# 13_USB3_0_power.net
KiCad netlist of a schematic drawn in Altium Designer
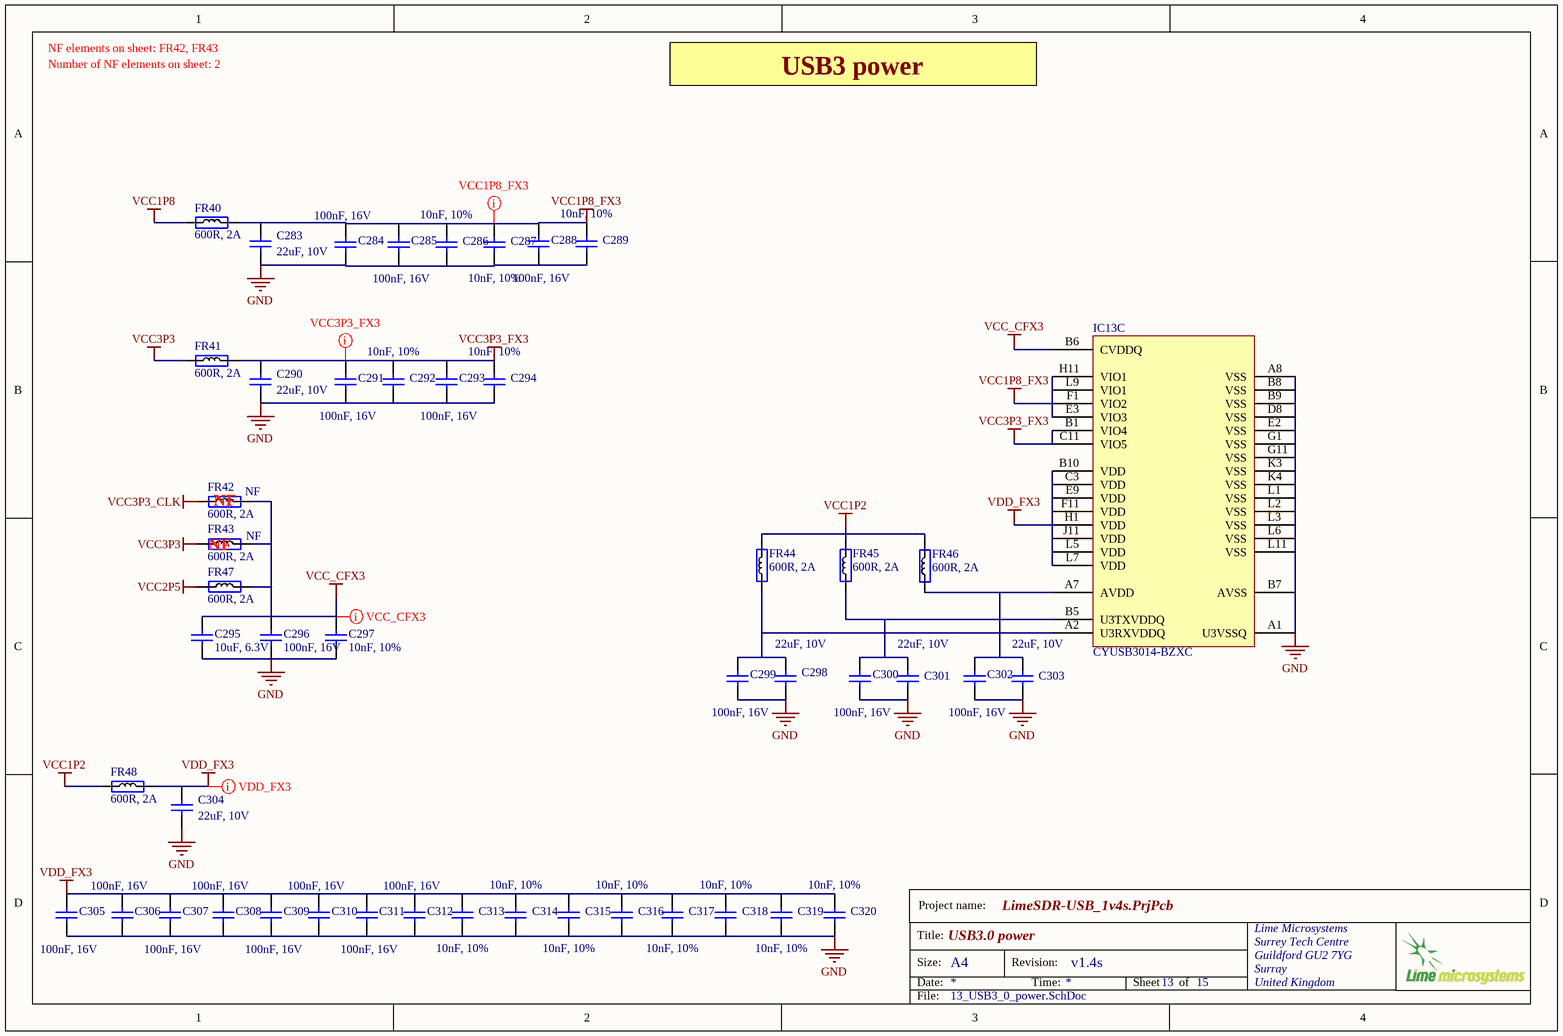
[diagram p0: 13_USB3_0_power.SchDoc]

(export (version "E")
  (design (tool "Eeschema 10.0.6"))
  (components
    (comp (ref "C283")
      (value "22uF, 10V")
      (footprint "CAP0603")
      (fields (field (name "TOLERANCE") "20 %") (field (name "MANUFACTURER") "TDK"))
      (libsource (lib "LimeFPGAboard_schLib") (part "Cap_0603"))
    )
    (comp (ref "C284")
      (value "100nF, 16V")
      (footprint "CAP0402")
      (fields
        (field (name "TOLERANCE") "10 %")
        (field (name "MANUFACTURER") "Murata Electronics")
        (field (name "MANUFACTURER PART NUMBER") "GRM155R71C104KA88D")
      )
      (libsource (lib "LimeFPGAboard_schLib") (part "Cap_0603"))
    )
    (comp (ref "C285")
      (value "100nF, 16V")
      (footprint "CAP0402")
      (fields
        (field (name "TOLERANCE") "10 %")
        (field (name "MANUFACTURER") "Murata Electronics")
        (field (name "MANUFACTURER PART NUMBER") "GRM155R71C104KA88D")
      )
      (libsource (lib "LimeFPGAboard_schLib") (part "Cap_0603"))
    )
    (comp (ref "C286")
      (value "10nF, 10%")
      (footprint "CAP0402")
      (fields (field (name "TOLERANCE") "±10%") (field (name "MANUFACTURER") "Yageo"))
      (libsource (lib "LimeFPGAboard_schLib") (part "Cap_0603"))
    )
    (comp (ref "C287")
      (value "10nF, 10%")
      (footprint "CAP0402")
      (fields (field (name "TOLERANCE") "±10%") (field (name "MANUFACTURER") "Yageo"))
      (libsource (lib "LimeFPGAboard_schLib") (part "Cap_0603"))
    )
    (comp (ref "C288")
      (value "100nF, 16V")
      (footprint "CAP0402")
      (fields
        (field (name "TOLERANCE") "10 %")
        (field (name "MANUFACTURER") "Murata Electronics")
        (field (name "MANUFACTURER PART NUMBER") "GRM155R71C104KA88D")
      )
      (libsource (lib "LimeFPGAboard_schLib") (part "Cap_0603"))
    )
    (comp (ref "C289")
      (value "10nF, 10%")
      (footprint "CAP0402")
      (fields (field (name "TOLERANCE") "±10%") (field (name "MANUFACTURER") "Yageo"))
      (libsource (lib "LimeFPGAboard_schLib") (part "Cap_0603"))
    )
    (comp (ref "C290")
      (value "22uF, 10V")
      (footprint "CAP0603")
      (fields (field (name "TOLERANCE") "20 %") (field (name "MANUFACTURER") "TDK"))
      (libsource (lib "LimeFPGAboard_schLib") (part "Cap_0603"))
    )
    (comp (ref "C291")
      (value "100nF, 16V")
      (footprint "CAP0402")
      (fields
        (field (name "TOLERANCE") "10 %")
        (field (name "MANUFACTURER") "Murata Electronics")
        (field (name "MANUFACTURER PART NUMBER") "GRM155R71C104KA88D")
      )
      (libsource (lib "LimeFPGAboard_schLib") (part "Cap_0603"))
    )
    (comp (ref "C292")
      (value "10nF, 10%")
      (footprint "CAP0402")
      (fields (field (name "TOLERANCE") "±10%") (field (name "MANUFACTURER") "Yageo"))
      (libsource (lib "LimeFPGAboard_schLib") (part "Cap_0603"))
    )
    (comp (ref "C293")
      (value "100nF, 16V")
      (footprint "CAP0402")
      (fields
        (field (name "TOLERANCE") "10 %")
        (field (name "MANUFACTURER") "Murata Electronics")
        (field (name "MANUFACTURER PART NUMBER") "GRM155R71C104KA88D")
      )
      (libsource (lib "LimeFPGAboard_schLib") (part "Cap_0603"))
    )
    (comp (ref "C294")
      (value "10nF, 10%")
      (footprint "CAP0402")
      (fields (field (name "TOLERANCE") "±10%") (field (name "MANUFACTURER") "Yageo"))
      (libsource (lib "LimeFPGAboard_schLib") (part "Cap_0603"))
    )
    (comp (ref "C295")
      (value "10uF, 6.3V")
      (footprint "CAP0603")
      (fields (field (name "TOLERANCE") "±20%") (field (name "MANUFACTURER") "Yageo"))
      (libsource (lib "LimeFPGAboard_schLib") (part "Cap_0603"))
    )
    (comp (ref "C296")
      (value "100nF, 16V")
      (footprint "CAP0402")
      (fields
        (field (name "TOLERANCE") "10 %")
        (field (name "MANUFACTURER") "Murata Electronics")
        (field (name "MANUFACTURER PART NUMBER") "GRM155R71C104KA88D")
      )
      (libsource (lib "LimeFPGAboard_schLib") (part "Cap_0603"))
    )
    (comp (ref "C297")
      (value "10nF, 10%")
      (footprint "CAP0402")
      (fields (field (name "TOLERANCE") "±10%") (field (name "MANUFACTURER") "Yageo"))
      (libsource (lib "LimeFPGAboard_schLib") (part "Cap_0603"))
    )
    (comp (ref "C298")
      (value "22uF, 10V")
      (footprint "CAP0603")
      (fields (field (name "TOLERANCE") "20 %") (field (name "MANUFACTURER") "TDK"))
      (libsource (lib "LimeFPGAboard_schLib") (part "Cap_0603"))
    )
    (comp (ref "C299")
      (value "100nF, 16V")
      (footprint "CAP0402")
      (fields
        (field (name "TOLERANCE") "10 %")
        (field (name "MANUFACTURER") "Murata Electronics")
        (field (name "MANUFACTURER PART NUMBER") "GRM155R71C104KA88D")
      )
      (libsource (lib "LimeFPGAboard_schLib") (part "Cap_0603"))
    )
    (comp (ref "C300")
      (value "100nF, 16V")
      (footprint "CAP0402")
      (fields
        (field (name "TOLERANCE") "10 %")
        (field (name "MANUFACTURER") "Murata Electronics")
        (field (name "MANUFACTURER PART NUMBER") "GRM155R71C104KA88D")
      )
      (libsource (lib "LimeFPGAboard_schLib") (part "Cap_0603"))
    )
    (comp (ref "C301")
      (value "22uF, 10V")
      (footprint "CAP0603")
      (fields (field (name "TOLERANCE") "20 %") (field (name "MANUFACTURER") "TDK"))
      (libsource (lib "LimeFPGAboard_schLib") (part "Cap_0603"))
    )
    (comp (ref "C302")
      (value "100nF, 16V")
      (footprint "CAP0402")
      (fields
        (field (name "TOLERANCE") "10 %")
        (field (name "MANUFACTURER") "Murata Electronics")
        (field (name "MANUFACTURER PART NUMBER") "GRM155R71C104KA88D")
      )
      (libsource (lib "LimeFPGAboard_schLib") (part "Cap_0603"))
    )
    (comp (ref "C303")
      (value "22uF, 10V")
      (footprint "CAP0603")
      (fields (field (name "TOLERANCE") "20 %") (field (name "MANUFACTURER") "TDK"))
      (libsource (lib "LimeFPGAboard_schLib") (part "Cap_0603"))
    )
    (comp (ref "C304")
      (value "22uF, 10V")
      (footprint "CAP0603")
      (fields (field (name "TOLERANCE") "20 %") (field (name "MANUFACTURER") "TDK"))
      (libsource (lib "LimeFPGAboard_schLib") (part "Cap_0603"))
    )
    (comp (ref "C305")
      (value "100nF, 16V")
      (footprint "CAP0402")
      (fields
        (field (name "TOLERANCE") "10 %")
        (field (name "MANUFACTURER") "Murata Electronics")
        (field (name "MANUFACTURER PART NUMBER") "GRM155R71C104KA88D")
      )
      (libsource (lib "LimeFPGAboard_schLib") (part "Cap_0603"))
    )
    (comp (ref "C306")
      (value "100nF, 16V")
      (footprint "CAP0402")
      (fields
        (field (name "TOLERANCE") "10 %")
        (field (name "MANUFACTURER") "Murata Electronics")
        (field (name "MANUFACTURER PART NUMBER") "GRM155R71C104KA88D")
      )
      (libsource (lib "LimeFPGAboard_schLib") (part "Cap_0603"))
    )
    (comp (ref "C307")
      (value "100nF, 16V")
      (footprint "CAP0402")
      (fields
        (field (name "TOLERANCE") "10 %")
        (field (name "MANUFACTURER") "Murata Electronics")
        (field (name "MANUFACTURER PART NUMBER") "GRM155R71C104KA88D")
      )
      (libsource (lib "LimeFPGAboard_schLib") (part "Cap_0603"))
    )
    (comp (ref "C308")
      (value "100nF, 16V")
      (footprint "CAP0402")
      (fields
        (field (name "TOLERANCE") "10 %")
        (field (name "MANUFACTURER") "Murata Electronics")
        (field (name "MANUFACTURER PART NUMBER") "GRM155R71C104KA88D")
      )
      (libsource (lib "LimeFPGAboard_schLib") (part "Cap_0603"))
    )
    (comp (ref "C309")
      (value "100nF, 16V")
      (footprint "CAP0402")
      (fields
        (field (name "TOLERANCE") "10 %")
        (field (name "MANUFACTURER") "Murata Electronics")
        (field (name "MANUFACTURER PART NUMBER") "GRM155R71C104KA88D")
      )
      (libsource (lib "LimeFPGAboard_schLib") (part "Cap_0603"))
    )
    (comp (ref "C310")
      (value "100nF, 16V")
      (footprint "CAP0402")
      (fields
        (field (name "TOLERANCE") "10 %")
        (field (name "MANUFACTURER") "Murata Electronics")
        (field (name "MANUFACTURER PART NUMBER") "GRM155R71C104KA88D")
      )
      (libsource (lib "LimeFPGAboard_schLib") (part "Cap_0603"))
    )
    (comp (ref "C311")
      (value "100nF, 16V")
      (footprint "CAP0402")
      (fields
        (field (name "TOLERANCE") "10 %")
        (field (name "MANUFACTURER") "Murata Electronics")
        (field (name "MANUFACTURER PART NUMBER") "GRM155R71C104KA88D")
      )
      (libsource (lib "LimeFPGAboard_schLib") (part "Cap_0603"))
    )
    (comp (ref "C312")
      (value "100nF, 16V")
      (footprint "CAP0402")
      (fields
        (field (name "TOLERANCE") "10 %")
        (field (name "MANUFACTURER") "Murata Electronics")
        (field (name "MANUFACTURER PART NUMBER") "GRM155R71C104KA88D")
      )
      (libsource (lib "LimeFPGAboard_schLib") (part "Cap_0603"))
    )
    (comp (ref "C313")
      (value "10nF, 10%")
      (footprint "CAP0402")
      (fields (field (name "TOLERANCE") "±10%") (field (name "MANUFACTURER") "Yageo"))
      (libsource (lib "LimeFPGAboard_schLib") (part "Cap_0603"))
    )
    (comp (ref "C314")
      (value "10nF, 10%")
      (footprint "CAP0402")
      (fields (field (name "TOLERANCE") "±10%") (field (name "MANUFACTURER") "Yageo"))
      (libsource (lib "LimeFPGAboard_schLib") (part "Cap_0603"))
    )
    (comp (ref "C315")
      (value "10nF, 10%")
      (footprint "CAP0402")
      (fields (field (name "TOLERANCE") "±10%") (field (name "MANUFACTURER") "Yageo"))
      (libsource (lib "LimeFPGAboard_schLib") (part "Cap_0603"))
    )
    (comp (ref "C316")
      (value "10nF, 10%")
      (footprint "CAP0402")
      (fields (field (name "TOLERANCE") "±10%") (field (name "MANUFACTURER") "Yageo"))
      (libsource (lib "LimeFPGAboard_schLib") (part "Cap_0603"))
    )
    (comp (ref "C317")
      (value "10nF, 10%")
      (footprint "CAP0402")
      (fields (field (name "TOLERANCE") "±10%") (field (name "MANUFACTURER") "Yageo"))
      (libsource (lib "LimeFPGAboard_schLib") (part "Cap_0603"))
    )
    (comp (ref "C318")
      (value "10nF, 10%")
      (footprint "CAP0402")
      (fields (field (name "TOLERANCE") "±10%") (field (name "MANUFACTURER") "Yageo"))
      (libsource (lib "LimeFPGAboard_schLib") (part "Cap_0603"))
    )
    (comp (ref "C319")
      (value "10nF, 10%")
      (footprint "CAP0402")
      (fields (field (name "TOLERANCE") "±10%") (field (name "MANUFACTURER") "Yageo"))
      (libsource (lib "LimeFPGAboard_schLib") (part "Cap_0603"))
    )
    (comp (ref "C320")
      (value "10nF, 10%")
      (footprint "CAP0402")
      (fields (field (name "TOLERANCE") "±10%") (field (name "MANUFACTURER") "Yageo"))
      (libsource (lib "LimeFPGAboard_schLib") (part "Cap_0603"))
    )
    (comp (ref "FR40")
      (value "600R, 2A")
      (footprint "RES0805")
      (fields (field (name "MANUFACTURER") "TDK Corporation"))
      (libsource (lib "") (part "Ferrite_1"))
    )
    (comp (ref "FR41")
      (value "600R, 2A")
      (footprint "RES0805")
      (fields (field (name "MANUFACTURER") "TDK Corporation"))
      (libsource (lib "") (part "Ferrite_1"))
    )
    (comp (ref "FR42")
      (value "600R, 2A")
      (footprint "RES0805")
      (fields (field (name "MANUFACTURER") "TDK Corporation") (field (name "ASSEMBLY INFO") "NF"))
      (libsource (lib "LimeFPGAboard_schLib") (part "Ferrite"))
    )
    (comp (ref "FR43")
      (value "600R, 2A")
      (footprint "RES0805")
      (fields (field (name "MANUFACTURER") "TDK Corporation") (field (name "ASSEMBLY INFO") "NF"))
      (libsource (lib "LimeFPGAboard_schLib") (part "Ferrite"))
    )
    (comp (ref "FR44")
      (value "600R, 2A")
      (footprint "RES0805")
      (fields (field (name "MANUFACTURER") "TDK Corporation"))
      (libsource (lib "") (part "Ferrite_1"))
    )
    (comp (ref "FR45")
      (value "600R, 2A")
      (footprint "RES0805")
      (fields (field (name "MANUFACTURER") "TDK Corporation"))
      (libsource (lib "") (part "Ferrite_1"))
    )
    (comp (ref "FR46")
      (value "600R, 2A")
      (footprint "RES0805")
      (fields (field (name "MANUFACTURER") "TDK Corporation"))
      (libsource (lib "") (part "Ferrite_1"))
    )
    (comp (ref "FR47")
      (value "600R, 2A")
      (footprint "RES0805")
      (fields (field (name "MANUFACTURER") "TDK Corporation"))
      (libsource (lib "LimeFPGAboard_schLib") (part "Ferrite"))
    )
    (comp (ref "FR48")
      (value "600R, 2A")
      (footprint "RES0805")
      (fields (field (name "MANUFACTURER") "TDK Corporation"))
      (libsource (lib "") (part "Ferrite_1"))
    )
    (comp (ref "IC13")
      (value "CYUSB3014-BZXC")
      (footprint "CYP-BZX121")
      (description "EZ-USB(R) FX3: SuperSpeed USB Controller, 512 KB, 60 I/Os, 0 to 70 degC, 121-Pin FBGA (BZX121)")
      (fields (field (name "MANUFACTURER") "Cypress Semiconductor Corp"))
      (libsource (lib "LimeMicroAltiumLib_schLib") (part "CYUSB3014-BZXC"))
    )
  )
  (nets
    (net (code "1") (name "GND") (class "Default")
      (node (ref "C283") (pin "1") (pinfunction "1_1") (pintype "passive"))
      (node (ref "C284") (pin "2") (pinfunction "2_2") (pintype "passive"))
      (node (ref "C285") (pin "2") (pinfunction "2_2") (pintype "passive"))
      (node (ref "C286") (pin "1") (pinfunction "1_1") (pintype "passive"))
      (node (ref "C287") (pin "1") (pinfunction "1_1") (pintype "passive"))
      (node (ref "C288") (pin "2") (pinfunction "2_2") (pintype "passive"))
      (node (ref "C289") (pin "1") (pinfunction "1_1") (pintype "passive"))
      (node (ref "C290") (pin "1") (pinfunction "1_1") (pintype "passive"))
      (node (ref "C291") (pin "2") (pinfunction "2_2") (pintype "passive"))
      (node (ref "C292") (pin "1") (pinfunction "1_1") (pintype "passive"))
      (node (ref "C293") (pin "2") (pinfunction "2_2") (pintype "passive"))
      (node (ref "C294") (pin "1") (pinfunction "1_1") (pintype "passive"))
      (node (ref "C295") (pin "1") (pinfunction "1_1") (pintype "passive"))
      (node (ref "C296") (pin "2") (pinfunction "2_2") (pintype "passive"))
      (node (ref "C297") (pin "1") (pinfunction "1_1") (pintype "passive"))
      (node (ref "C298") (pin "1") (pinfunction "1_1") (pintype "passive"))
      (node (ref "C299") (pin "2") (pinfunction "2_2") (pintype "passive"))
      (node (ref "C300") (pin "2") (pinfunction "2_2") (pintype "passive"))
      (node (ref "C301") (pin "1") (pinfunction "1_1") (pintype "passive"))
      (node (ref "C302") (pin "2") (pinfunction "2_2") (pintype "passive"))
      (node (ref "C303") (pin "1") (pinfunction "1_1") (pintype "passive"))
      (node (ref "C304") (pin "1") (pinfunction "1_1") (pintype "passive"))
      (node (ref "C305") (pin "2") (pinfunction "2_2") (pintype "passive"))
      (node (ref "C306") (pin "2") (pinfunction "2_2") (pintype "passive"))
      (node (ref "C307") (pin "2") (pinfunction "2_2") (pintype "passive"))
      (node (ref "C308") (pin "2") (pinfunction "2_2") (pintype "passive"))
      (node (ref "C309") (pin "2") (pinfunction "2_2") (pintype "passive"))
      (node (ref "C310") (pin "2") (pinfunction "2_2") (pintype "passive"))
      (node (ref "C311") (pin "2") (pinfunction "2_2") (pintype "passive"))
      (node (ref "C312") (pin "2") (pinfunction "2_2") (pintype "passive"))
      (node (ref "C313") (pin "1") (pinfunction "1_1") (pintype "passive"))
      (node (ref "C314") (pin "1") (pinfunction "1_1") (pintype "passive"))
      (node (ref "C315") (pin "1") (pinfunction "1_1") (pintype "passive"))
      (node (ref "C316") (pin "1") (pinfunction "1_1") (pintype "passive"))
      (node (ref "C317") (pin "1") (pinfunction "1_1") (pintype "passive"))
      (node (ref "C318") (pin "1") (pinfunction "1_1") (pintype "passive"))
      (node (ref "C319") (pin "1") (pinfunction "1_1") (pintype "passive"))
      (node (ref "C320") (pin "1") (pinfunction "1_1") (pintype "passive"))
      (node (ref "IC13") (pin "A1") (pinfunction "U3VSSQ_A1") (pintype "power_in"))
      (node (ref "IC13") (pin "A8") (pinfunction "VSS_A8") (pintype "power_in"))
      (node (ref "IC13") (pin "B7") (pinfunction "AVSS_B7") (pintype "power_in"))
      (node (ref "IC13") (pin "B8") (pinfunction "VSS_B8") (pintype "power_in"))
      (node (ref "IC13") (pin "B9") (pinfunction "VSS_B9") (pintype "power_in"))
      (node (ref "IC13") (pin "D8") (pinfunction "VSS_D8") (pintype "power_in"))
      (node (ref "IC13") (pin "E2") (pinfunction "VSS_E2") (pintype "power_in"))
      (node (ref "IC13") (pin "G1") (pinfunction "VSS_G1") (pintype "power_in"))
      (node (ref "IC13") (pin "G11") (pinfunction "VSS_G11") (pintype "power_in"))
      (node (ref "IC13") (pin "K3") (pinfunction "VSS_K3") (pintype "power_in"))
      (node (ref "IC13") (pin "K4") (pinfunction "VSS_K4") (pintype "power_in"))
      (node (ref "IC13") (pin "L1") (pinfunction "VSS_L1") (pintype "power_in"))
      (node (ref "IC13") (pin "L11") (pinfunction "VSS_L11") (pintype "power_in"))
      (node (ref "IC13") (pin "L2") (pinfunction "VSS_L2") (pintype "power_in"))
      (node (ref "IC13") (pin "L3") (pinfunction "VSS_L3") (pintype "power_in"))
      (node (ref "IC13") (pin "L6") (pinfunction "VSS_L6") (pintype "power_in"))
    )
    (net (code "2") (name "Net-(IC13C-AVDD)") (class "Default")
      (node (ref "C302") (pin "1") (pinfunction "1_1") (pintype "passive"))
      (node (ref "C303") (pin "2") (pinfunction "2_2") (pintype "passive"))
      (node (ref "FR46") (pin "1") (pinfunction "1_1") (pintype "passive"))
      (node (ref "IC13") (pin "A7") (pinfunction "AVDD_A7") (pintype "power_in"))
    )
    (net (code "3") (name "Net-(IC13C-U3RXVDDQ)") (class "Default")
      (node (ref "C298") (pin "2") (pinfunction "2_2") (pintype "passive"))
      (node (ref "C299") (pin "1") (pinfunction "1_1") (pintype "passive"))
      (node (ref "FR44") (pin "1") (pinfunction "1_1") (pintype "passive"))
      (node (ref "IC13") (pin "A2") (pinfunction "U3RXVDDQ_A2") (pintype "power_in"))
    )
    (net (code "4") (name "Net-(IC13C-U3TXVDDQ)") (class "Default")
      (node (ref "C300") (pin "1") (pinfunction "1_1") (pintype "passive"))
      (node (ref "C301") (pin "2") (pinfunction "2_2") (pintype "passive"))
      (node (ref "FR45") (pin "1") (pinfunction "1_1") (pintype "passive"))
      (node (ref "IC13") (pin "B5") (pinfunction "U3TXVDDQ_B5") (pintype "power_in"))
    )
    (net (code "5") (name "VCC1P2") (class "Default")
      (node (ref "FR44") (pin "2") (pinfunction "2_2") (pintype "passive"))
      (node (ref "FR45") (pin "2") (pinfunction "2_2") (pintype "passive"))
      (node (ref "FR46") (pin "2") (pinfunction "2_2") (pintype "passive"))
      (node (ref "FR48") (pin "1") (pinfunction "1_1") (pintype "passive"))
    )
    (net (code "6") (name "VCC1P8") (class "Default")
      (node (ref "FR40") (pin "1") (pinfunction "1_1") (pintype "passive"))
    )
    (net (code "7") (name "VCC1P8_FX3") (class "Default")
      (node (ref "C283") (pin "2") (pinfunction "2_2") (pintype "passive"))
      (node (ref "C284") (pin "1") (pinfunction "1_1") (pintype "passive"))
      (node (ref "C285") (pin "1") (pinfunction "1_1") (pintype "passive"))
      (node (ref "C286") (pin "2") (pinfunction "2_2") (pintype "passive"))
      (node (ref "C287") (pin "2") (pinfunction "2_2") (pintype "passive"))
      (node (ref "C288") (pin "1") (pinfunction "1_1") (pintype "passive"))
      (node (ref "C289") (pin "2") (pinfunction "2_2") (pintype "passive"))
      (node (ref "FR40") (pin "2") (pinfunction "2_2") (pintype "passive"))
      (node (ref "IC13") (pin "E3") (pinfunction "VIO3_E3") (pintype "power_in"))
      (node (ref "IC13") (pin "F1") (pinfunction "VIO2_F1") (pintype "power_in"))
      (node (ref "IC13") (pin "H11") (pinfunction "VIO1_H11") (pintype "power_in"))
      (node (ref "IC13") (pin "L9") (pinfunction "VIO1_L9") (pintype "power_in"))
    )
    (net (code "8") (name "VCC2P5") (class "Default")
      (node (ref "FR47") (pin "2") (pinfunction "2_2") (pintype "passive"))
    )
    (net (code "9") (name "VCC3P3") (class "Default")
      (node (ref "FR41") (pin "1") (pinfunction "1_1") (pintype "passive"))
      (node (ref "FR43") (pin "2") (pinfunction "2_2") (pintype "passive"))
    )
    (net (code "10") (name "VCC3P3_CLK") (class "Default")
      (node (ref "FR42") (pin "2") (pinfunction "2_2") (pintype "passive"))
    )
    (net (code "11") (name "VCC3P3_FX3") (class "Default")
      (node (ref "C290") (pin "2") (pinfunction "2_2") (pintype "passive"))
      (node (ref "C291") (pin "1") (pinfunction "1_1") (pintype "passive"))
      (node (ref "C292") (pin "2") (pinfunction "2_2") (pintype "passive"))
      (node (ref "C293") (pin "1") (pinfunction "1_1") (pintype "passive"))
      (node (ref "C294") (pin "2") (pinfunction "2_2") (pintype "passive"))
      (node (ref "FR41") (pin "2") (pinfunction "2_2") (pintype "passive"))
      (node (ref "IC13") (pin "B1") (pinfunction "VIO4_B1") (pintype "power_in"))
      (node (ref "IC13") (pin "C11") (pinfunction "VIO5_C11") (pintype "power_in"))
    )
    (net (code "12") (name "VCC_CFX3") (class "Default")
      (node (ref "C295") (pin "2") (pinfunction "2_2") (pintype "passive"))
      (node (ref "C296") (pin "1") (pinfunction "1_1") (pintype "passive"))
      (node (ref "C297") (pin "2") (pinfunction "2_2") (pintype "passive"))
      (node (ref "FR42") (pin "1") (pinfunction "1_1") (pintype "passive"))
      (node (ref "FR43") (pin "1") (pinfunction "1_1") (pintype "passive"))
      (node (ref "FR47") (pin "1") (pinfunction "1_1") (pintype "passive"))
      (node (ref "IC13") (pin "B6") (pinfunction "CVDDQ_B6") (pintype "power_in"))
    )
    (net (code "13") (name "VDD_FX3") (class "Default")
      (node (ref "C304") (pin "2") (pinfunction "2_2") (pintype "passive"))
      (node (ref "C305") (pin "1") (pinfunction "1_1") (pintype "passive"))
      (node (ref "C306") (pin "1") (pinfunction "1_1") (pintype "passive"))
      (node (ref "C307") (pin "1") (pinfunction "1_1") (pintype "passive"))
      (node (ref "C308") (pin "1") (pinfunction "1_1") (pintype "passive"))
      (node (ref "C309") (pin "1") (pinfunction "1_1") (pintype "passive"))
      (node (ref "C310") (pin "1") (pinfunction "1_1") (pintype "passive"))
      (node (ref "C311") (pin "1") (pinfunction "1_1") (pintype "passive"))
      (node (ref "C312") (pin "1") (pinfunction "1_1") (pintype "passive"))
      (node (ref "C313") (pin "2") (pinfunction "2_2") (pintype "passive"))
      (node (ref "C314") (pin "2") (pinfunction "2_2") (pintype "passive"))
      (node (ref "C315") (pin "2") (pinfunction "2_2") (pintype "passive"))
      (node (ref "C316") (pin "2") (pinfunction "2_2") (pintype "passive"))
      (node (ref "C317") (pin "2") (pinfunction "2_2") (pintype "passive"))
      (node (ref "C318") (pin "2") (pinfunction "2_2") (pintype "passive"))
      (node (ref "C319") (pin "2") (pinfunction "2_2") (pintype "passive"))
      (node (ref "C320") (pin "2") (pinfunction "2_2") (pintype "passive"))
      (node (ref "FR48") (pin "2") (pinfunction "2_2") (pintype "passive"))
      (node (ref "IC13") (pin "B10") (pinfunction "VDD_B10") (pintype "power_in"))
      (node (ref "IC13") (pin "C3") (pinfunction "VDD_C3") (pintype "power_in"))
      (node (ref "IC13") (pin "E9") (pinfunction "VDD_E9") (pintype "power_in"))
      (node (ref "IC13") (pin "F11") (pinfunction "VDD_F11") (pintype "power_in"))
      (node (ref "IC13") (pin "H1") (pinfunction "VDD_H1") (pintype "power_in"))
      (node (ref "IC13") (pin "J11") (pinfunction "VDD_J11") (pintype "power_in"))
      (node (ref "IC13") (pin "L5") (pinfunction "VDD_L5") (pintype "power_in"))
      (node (ref "IC13") (pin "L7") (pinfunction "VDD_L7") (pintype "power_in"))
    )
  )
)
